# PrototypeBoardV2B.net
KiCad netlist of a schematic drawn in EasyEDA Pro
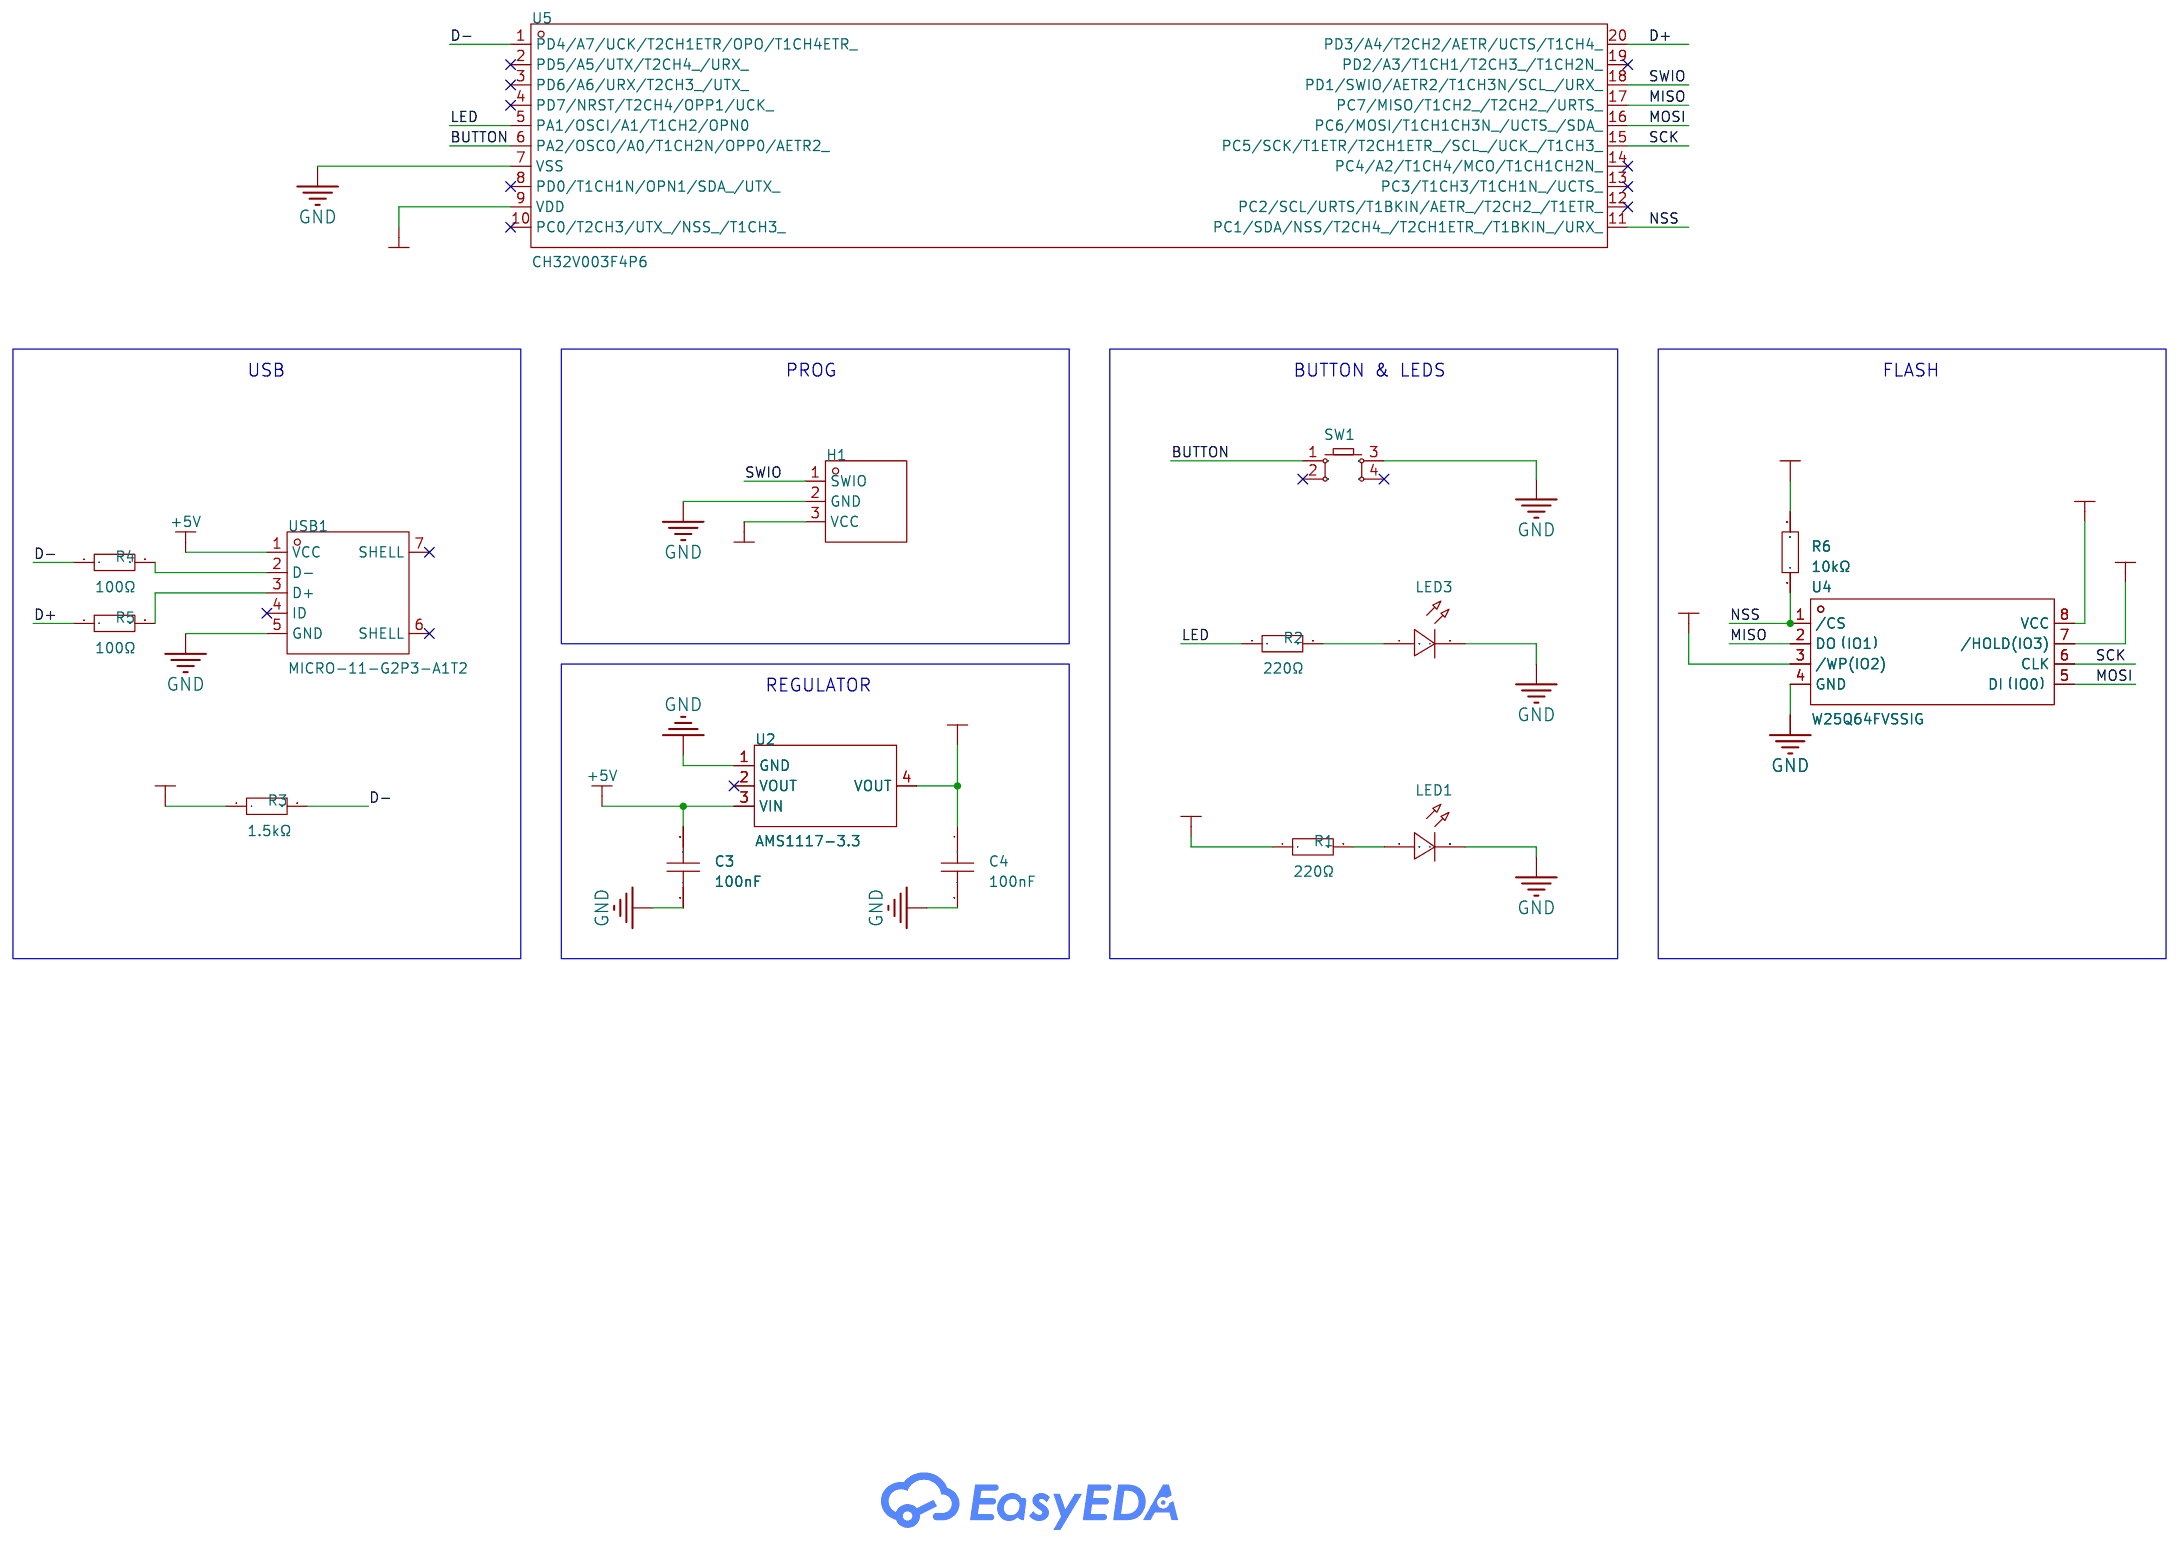
[diagram p0: schematic sheet]

(export (version "E")
  (design (tool "Eeschema 10.0.6"))
  (components
    (comp (ref "C3")
      (value "100nF")
      (footprint "easyedapro:CAP-TH_L5.8-W3.0-P4.7-D0.45")
      (fields (field (name "Manufacturer Part") "1C10Z5U104M050B") (field (name "Manufacturer") "VISHAY(威世)"))
      (libsource (lib "easyedapro") (part "1C10Z5U104M050B"))
    )
    (comp (ref "C4")
      (value "100nF")
      (footprint "easyedapro:CAP-TH_L5.8-W3.0-P4.7-D0.45")
      (fields (field (name "Manufacturer Part") "1C10Z5U104M050B") (field (name "Manufacturer") "VISHAY(威世)"))
      (libsource (lib "easyedapro") (part "1C10Z5U104M050B"))
    )
    (comp (ref "H1")
      (value "~")
      (footprint "easyedapro:HDR-TH_3P-P2.54-V-M")
      (libsource (lib "easyedapro") (part "PZ254V-11-03P_C2937625"))
    )
    (comp (ref "LED1")
      (value "~")
      (footprint "easyedapro:LED-TH_BD3.0-P2.54-FD")
      (libsource (lib "easyedapro") (part "LED_TH-R"))
    )
    (comp (ref "LED3")
      (value "~")
      (footprint "easyedapro:LED-TH_BD5.0-P2.54-L-RD_WHITE")
      (libsource (lib "easyedapro") (part "LED_TH-B"))
    )
    (comp (ref "R1")
      (value "220Ω")
      (footprint "easyedapro:RES-TH_BD1.8-L3.2-P7.20-D0.4")
      (libsource (lib "easyedapro") (part "Res"))
    )
    (comp (ref "R2")
      (value "220Ω")
      (footprint "easyedapro:RES-TH_BD1.8-L3.2-P7.20-D0.4")
      (libsource (lib "easyedapro") (part "Res"))
    )
    (comp (ref "R3")
      (value "1.5kΩ")
      (footprint "easyedapro:RES-TH_BD1.8-L3.2-P7.20-D0.4")
      (libsource (lib "easyedapro") (part "Res"))
    )
    (comp (ref "R4")
      (value "100Ω")
      (footprint "easyedapro:RES-TH_BD1.8-L3.2-P7.20-D0.4")
      (libsource (lib "easyedapro") (part "Res"))
    )
    (comp (ref "R5")
      (value "100Ω")
      (footprint "easyedapro:RES-TH_BD1.8-L3.2-P7.20-D0.4")
      (libsource (lib "easyedapro") (part "Res"))
    )
    (comp (ref "R6")
      (value "10kΩ")
      (footprint "easyedapro:RES-TH_BD1.8-L3.2-P7.20-D0.4")
      (libsource (lib "easyedapro") (part "Res"))
    )
    (comp (ref "SW1")
      (value "~")
      (footprint "easyedapro:KEY-TH_4P-L6.0-W6.0-P3.90-LS6.5")
      (libsource (lib "easyedapro") (part "轻触按键"))
    )
    (comp (ref "U2")
      (value "AMS1117-3.3")
      (footprint "easyedapro:SOT-223-3_L6.5-W3.4-P2.30-LS7.0-BR")
      (fields (field (name "Manufacturer") "AMS"))
      (libsource (lib "easyedapro") (part "AMS1117-3.3"))
    )
    (comp (ref "U4")
      (value "W25Q64FVSSIG")
      (footprint "easyedapro:SOIC-8_L5.3-W5.3-P1.27-LS8.0-BL")
      (libsource (lib "easyedapro") (part "W25Q64FVSSIG_C66141"))
    )
    (comp (ref "U5")
      (value "CH32V003F4P6")
      (footprint "easyedapro:TSSOP-20_L6.5-W4.4-P0.65-LS6.4-BL")
      (fields (field (name "Manufacturer") "WCH(南京沁恒)"))
      (libsource (lib "easyedapro") (part "CH32V003F4P6"))
    )
    (comp (ref "USB1")
      (value "MICRO-11-G2P3-A1T2")
      (footprint "easyedapro:MICRO-USB-SMD_MICRO-12-G2P3-A1T2")
      (fields (field (name "Manufacturer") "Yuandi(元迪)"))
      (libsource (lib "easyedapro") (part "MICRO-11-G2P3-A1T2"))
    )
  )
  (nets
    (net (code "1") (name "+3.3V") (class "Default")
      (node (ref "C4") (pin "1") (pinfunction "1_1") (pintype "unspecified"))
      (node (ref "H1") (pin "3") (pinfunction "VCC_3") (pintype "unspecified"))
      (node (ref "R1") (pin "1") (pinfunction "1_1") (pintype "input"))
      (node (ref "R3") (pin "1") (pinfunction "1_1") (pintype "input"))
      (node (ref "R6") (pin "2") (pinfunction "2_2") (pintype "input"))
      (node (ref "U2") (pin "4") (pinfunction "VOUT_4") (pintype "unspecified"))
      (node (ref "U4") (pin "3") (pinfunction "/WP(IO2)_3") (pintype "unspecified"))
      (node (ref "U4") (pin "7") (pinfunction "/HOLD(IO3)_7") (pintype "unspecified"))
      (node (ref "U4") (pin "8") (pinfunction "VCC_8") (pintype "unspecified"))
      (node (ref "U5") (pin "9") (pinfunction "VDD_9") (pintype "unspecified"))
    )
    (net (code "2") (name "+5V") (class "Default")
      (node (ref "C3") (pin "2") (pinfunction "2_2") (pintype "unspecified"))
      (node (ref "U2") (pin "3") (pinfunction "VIN_3") (pintype "unspecified"))
      (node (ref "USB1") (pin "1") (pinfunction "VCC_1") (pintype "unspecified"))
    )
    (net (code "3") (name "/BUTTON") (class "Default")
      (node (ref "SW1") (pin "1") (pinfunction "1_1") (pintype "input"))
      (node (ref "U5") (pin "6") (pinfunction "PA2/OSCO/A0/T1CH2N/OPP0/AETR2__6") (pintype "unspecified"))
    )
    (net (code "4") (name "/D+") (class "Default")
      (node (ref "R5") (pin "1") (pinfunction "1_1") (pintype "input"))
      (node (ref "U5") (pin "20") (pinfunction "PD3/A4/T2CH2/AETR/UCTS/T1CH4__20") (pintype "unspecified"))
    )
    (net (code "5") (name "/D-") (class "Default")
      (node (ref "R3") (pin "2") (pinfunction "2_2") (pintype "input"))
      (node (ref "R4") (pin "1") (pinfunction "1_1") (pintype "input"))
      (node (ref "U5") (pin "1") (pinfunction "PD4/A7/UCK/T2CH1ETR/OPO/T1CH4ETR__1") (pintype "unspecified"))
    )
    (net (code "6") (name "/LED") (class "Default")
      (node (ref "R2") (pin "1") (pinfunction "1_1") (pintype "input"))
      (node (ref "U5") (pin "5") (pinfunction "PA1/OSCI/A1/T1CH2/OPN0_5") (pintype "unspecified"))
    )
    (net (code "7") (name "/MISO") (class "Default")
      (node (ref "U4") (pin "2") (pinfunction "DO（IO1）_2") (pintype "unspecified"))
      (node (ref "U5") (pin "17") (pinfunction "PC7/MISO/T1CH2_/T2CH2_/URTS__17") (pintype "unspecified"))
    )
    (net (code "8") (name "/MOSI") (class "Default")
      (node (ref "U4") (pin "5") (pinfunction "DI（IO0）_5") (pintype "unspecified"))
      (node (ref "U5") (pin "16") (pinfunction "PC6/MOSI/T1CH1CH3N_/UCTS_/SDA__16") (pintype "unspecified"))
    )
    (net (code "9") (name "/NSS") (class "Default")
      (node (ref "R6") (pin "1") (pinfunction "1_1") (pintype "input"))
      (node (ref "U4") (pin "1") (pinfunction "/CS_1") (pintype "unspecified"))
      (node (ref "U5") (pin "11") (pinfunction "PC1/SDA/NSS/T2CH4_/T2CH1ETR_/T1BKIN_/URX__11") (pintype "unspecified"))
    )
    (net (code "10") (name "/SCK") (class "Default")
      (node (ref "U4") (pin "6") (pinfunction "CLK_6") (pintype "unspecified"))
      (node (ref "U5") (pin "15") (pinfunction "PC5/SCK/T1ETR/T2CH1ETR_/SCL_/UCK_/T1CH3__15") (pintype "unspecified"))
    )
    (net (code "11") (name "/SWIO") (class "Default")
      (node (ref "H1") (pin "1") (pinfunction "SWIO_1") (pintype "unspecified"))
      (node (ref "U5") (pin "18") (pinfunction "PD1/SWIO/AETR2/T1CH3N/SCL_/URX__18") (pintype "unspecified"))
    )
    (net (code "12") (name "GND") (class "Default")
      (node (ref "C3") (pin "1") (pinfunction "1_1") (pintype "unspecified"))
      (node (ref "C4") (pin "2") (pinfunction "2_2") (pintype "unspecified"))
      (node (ref "H1") (pin "2") (pinfunction "GND_2") (pintype "unspecified"))
      (node (ref "LED1") (pin "2") (pinfunction "A_2") (pintype "input"))
      (node (ref "LED3") (pin "2") (pinfunction "A_2") (pintype "input"))
      (node (ref "SW1") (pin "3") (pinfunction "3_3") (pintype "input"))
      (node (ref "U2") (pin "1") (pinfunction "GND_1") (pintype "unspecified"))
      (node (ref "U4") (pin "4") (pinfunction "GND_4") (pintype "unspecified"))
      (node (ref "U5") (pin "7") (pinfunction "VSS_7") (pintype "unspecified"))
      (node (ref "USB1") (pin "5") (pinfunction "GND_5") (pintype "unspecified"))
    )
    (net (code "13") (name "Net-(LED1-C)") (class "Default")
      (node (ref "LED1") (pin "1") (pinfunction "C_1") (pintype "input"))
      (node (ref "R1") (pin "2") (pinfunction "2_2") (pintype "input"))
    )
    (net (code "14") (name "Net-(LED3-C)") (class "Default")
      (node (ref "LED3") (pin "1") (pinfunction "C_1") (pintype "input"))
      (node (ref "R2") (pin "2") (pinfunction "2_2") (pintype "input"))
    )
    (net (code "15") (name "Net-(USB1-D+)") (class "Default")
      (node (ref "R5") (pin "2") (pinfunction "2_2") (pintype "input"))
      (node (ref "USB1") (pin "3") (pinfunction "D+_3") (pintype "unspecified"))
    )
    (net (code "16") (name "Net-(USB1-D-)") (class "Default")
      (node (ref "R4") (pin "2") (pinfunction "2_2") (pintype "input"))
      (node (ref "USB1") (pin "2") (pinfunction "D-_2") (pintype "unspecified"))
    )
    (net (code "17") (name "unconnected-(SW1-Pad2)") (class "Default")
      (node (ref "SW1") (pin "2") (pinfunction "2_2") (pintype "input+no_connect"))
    )
    (net (code "18") (name "unconnected-(SW1-Pad4)") (class "Default")
      (node (ref "SW1") (pin "4") (pinfunction "4_4") (pintype "input+no_connect"))
    )
    (net (code "19") (name "unconnected-(U2-VOUT-Pad2)") (class "Default")
      (node (ref "U2") (pin "2") (pinfunction "VOUT_2") (pintype "unspecified+no_connect"))
    )
    (net (code "20") (name "unconnected-(U5-PC0{slash}T2CH3{slash}UTX_{slash}NSS_{slash}T1CH3_-Pad10)") (class "Default")
      (node (ref "U5") (pin "10") (pinfunction "PC0/T2CH3/UTX_/NSS_/T1CH3__10") (pintype "unspecified+no_connect"))
    )
    (net (code "21") (name "unconnected-(U5-PC2{slash}SCL{slash}URTS{slash}T1BKIN{slash}AETR_{slash}T2CH2_{slash}T1ETR_-Pad12)") (class "Default")
      (node (ref "U5") (pin "12") (pinfunction "PC2/SCL/URTS/T1BKIN/AETR_/T2CH2_/T1ETR__12") (pintype "unspecified+no_connect"))
    )
    (net (code "22") (name "unconnected-(U5-PC3{slash}T1CH3{slash}T1CH1N_{slash}UCTS_-Pad13)") (class "Default")
      (node (ref "U5") (pin "13") (pinfunction "PC3/T1CH3/T1CH1N_/UCTS__13") (pintype "unspecified+no_connect"))
    )
    (net (code "23") (name "unconnected-(U5-PC4{slash}A2{slash}T1CH4{slash}MCO{slash}T1CH1CH2N_-Pad14)") (class "Default")
      (node (ref "U5") (pin "14") (pinfunction "PC4/A2/T1CH4/MCO/T1CH1CH2N__14") (pintype "unspecified+no_connect"))
    )
    (net (code "24") (name "unconnected-(U5-PD0{slash}T1CH1N{slash}OPN1{slash}SDA_{slash}UTX_-Pad8)") (class "Default")
      (node (ref "U5") (pin "8") (pinfunction "PD0/T1CH1N/OPN1/SDA_/UTX__8") (pintype "unspecified+no_connect"))
    )
    (net (code "25") (name "unconnected-(U5-PD2{slash}A3{slash}T1CH1{slash}T2CH3_{slash}T1CH2N_-Pad19)") (class "Default")
      (node (ref "U5") (pin "19") (pinfunction "PD2/A3/T1CH1/T2CH3_/T1CH2N__19") (pintype "unspecified+no_connect"))
    )
    (net (code "26") (name "unconnected-(U5-PD5{slash}A5{slash}UTX{slash}T2CH4_{slash}URX_-Pad2)") (class "Default")
      (node (ref "U5") (pin "2") (pinfunction "PD5/A5/UTX/T2CH4_/URX__2") (pintype "unspecified+no_connect"))
    )
    (net (code "27") (name "unconnected-(U5-PD6{slash}A6{slash}URX{slash}T2CH3_{slash}UTX_-Pad3)") (class "Default")
      (node (ref "U5") (pin "3") (pinfunction "PD6/A6/URX/T2CH3_/UTX__3") (pintype "unspecified+no_connect"))
    )
    (net (code "28") (name "unconnected-(U5-PD7{slash}NRST{slash}T2CH4{slash}OPP1{slash}UCK_-Pad4)") (class "Default")
      (node (ref "U5") (pin "4") (pinfunction "PD7/NRST/T2CH4/OPP1/UCK__4") (pintype "unspecified+no_connect"))
    )
    (net (code "29") (name "unconnected-(USB1-ID-Pad4)") (class "Default")
      (node (ref "USB1") (pin "4") (pinfunction "ID_4") (pintype "unspecified+no_connect"))
    )
    (net (code "30") (name "unconnected-(USB1-SHELL-Pad6)") (class "Default")
      (node (ref "USB1") (pin "6") (pinfunction "SHELL_6") (pintype "unspecified+no_connect"))
    )
    (net (code "31") (name "unconnected-(USB1-SHELL-Pad7)") (class "Default")
      (node (ref "USB1") (pin "7") (pinfunction "SHELL_7") (pintype "unspecified+no_connect"))
    )
  )
)
